# zigbee-plant-sensor-v1_1.net
KiCad netlist of a schematic drawn in EasyEDA Pro
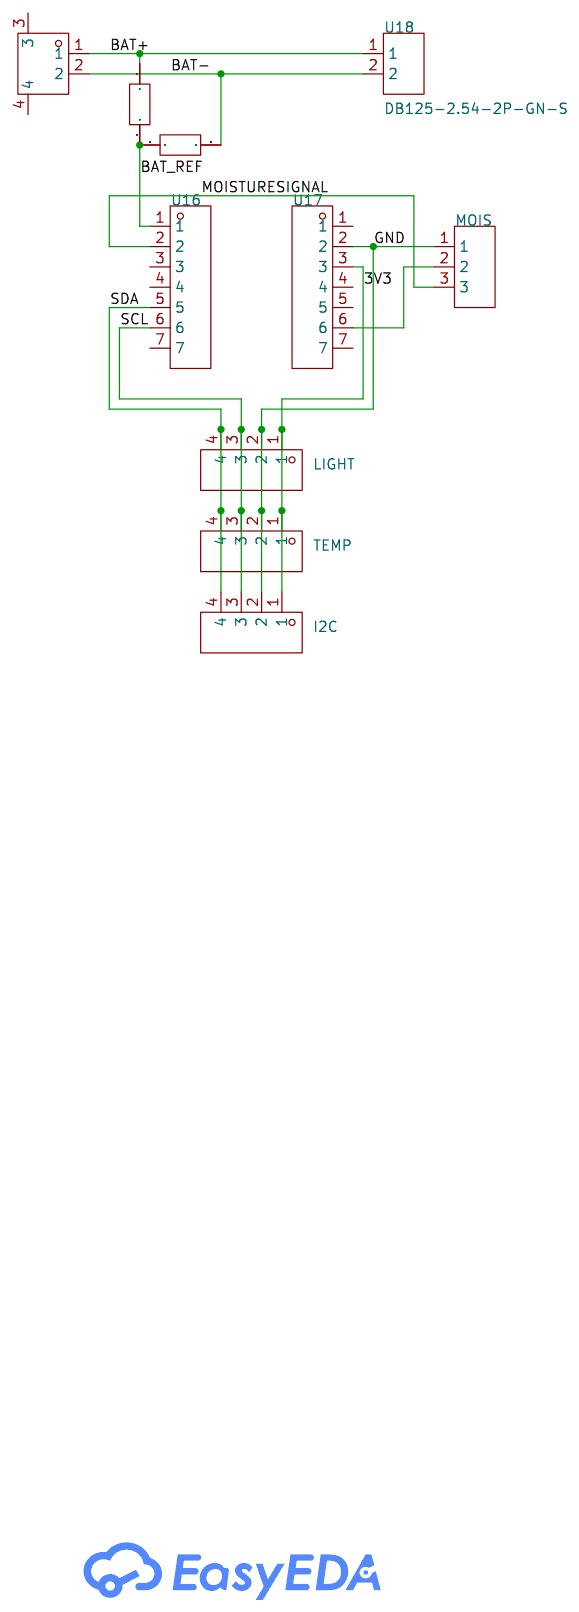
[diagram p0: schematic sheet]

(export (version "E")
  (design (tool "Eeschema 10.0.6"))
  (components
    (comp (ref "CN1")
      (value "JST-PH-2-SMT-RA")
      (footprint "easyedapro:CONN-SMD_JST-PH-2-SMT-RA")
      (libsource (lib "easyedapro") (part "JST-PH-2-SMT-RA"))
    )
    (comp (ref "I2C")
      (value "5BML8-11732-104-W0")
      (footprint "easyedapro:CONN-TH_5BML8-11732-104-W0")
      (fields (field (name "Manufacturer") "SAMZO(三佐)"))
      (libsource (lib "easyedapro") (part "5BML8-11732-104-W0"))
    )
    (comp (ref "LIGHT")
      (value "5BML8-11732-104-W0")
      (footprint "easyedapro:CONN-TH_5BML8-11732-104-W0")
      (fields (field (name "Manufacturer") "SAMZO(三佐)"))
      (libsource (lib "easyedapro") (part "5BML8-11732-104-W0"))
    )
    (comp (ref "MOIS")
      (value "HTSW-103-07-S-S")
      (footprint "easyedapro:HDR-TH_3P-P2.54-V-M-1")
      (fields (field (name "Manufacturer") "SAMTEC"))
      (libsource (lib "easyedapro") (part "HTSW-103-07-S-S"))
    )
    (comp (ref "R1")
      (value "200kΩ")
      (footprint "easyedapro:RES-TH_BD2.5-L7.0-P11.00-D0.6")
      (description "Type:Carbon Composite Resistor Resistance:200kΩ Tolerance:±5% Tolerance:±5% Power(Watts):250mW")
      (fields (field (name "Manufacturer Part") "OD204J") (field (name "Manufacturer") "Ohmite"))
      (libsource (lib "easyedapro") (part "OD204J"))
    )
    (comp (ref "R2")
      (value "200kΩ")
      (footprint "easyedapro:RES-TH_BD2.5-L7.0-P11.00-D0.6")
      (description "Type:Carbon Composite Resistor Resistance:200kΩ Tolerance:±5% Tolerance:±5% Power(Watts):250mW")
      (fields (field (name "Manufacturer Part") "OD204J") (field (name "Manufacturer") "Ohmite"))
      (libsource (lib "easyedapro") (part "OD204J"))
    )
    (comp (ref "TEMP")
      (value "5BML8-11732-104-W0")
      (footprint "easyedapro:CONN-TH_5BML8-11732-104-W0")
      (fields (field (name "Manufacturer") "SAMZO(三佐)"))
      (libsource (lib "easyedapro") (part "5BML8-11732-104-W0"))
    )
    (comp (ref "U16")
      (value "IPCP254F07PB08V")
      (footprint "easyedapro:HDR-TH_7P-P2.54-V-F")
      (fields (field (name "Manufacturer") "INCP"))
      (libsource (lib "easyedapro") (part "IPCP254F07PB08V"))
    )
    (comp (ref "U17")
      (value "IPCP254F07PB08V")
      (footprint "easyedapro:HDR-TH_7P-P2.54-V-F")
      (fields (field (name "Manufacturer") "INCP"))
      (libsource (lib "easyedapro") (part "IPCP254F07PB08V"))
    )
    (comp (ref "U18")
      (value "DB125-2.54-2P-GN-S")
      (footprint "easyedapro:CONN-TH_DB125-2.54-2P-GN")
      (fields (field (name "Manufacturer") "DORABO(地博电气)"))
      (libsource (lib "easyedapro") (part "DB125-2.54-2P-GN"))
    )
  )
  (nets
    (net (code "1") (name "/3V3") (class "Default")
      (node (ref "I2C") (pin "1") (pinfunction "1_1") (pintype "unspecified"))
      (node (ref "LIGHT") (pin "1") (pinfunction "1_1") (pintype "unspecified"))
      (node (ref "TEMP") (pin "1") (pinfunction "1_1") (pintype "unspecified"))
      (node (ref "U17") (pin "3") (pinfunction "3_3") (pintype "unspecified"))
    )
    (net (code "2") (name "/BAT+") (class "Default")
      (node (ref "CN1") (pin "1") (pinfunction "1_1") (pintype "unspecified"))
      (node (ref "R1") (pin "1") (pinfunction "1_1") (pintype "unspecified"))
      (node (ref "U18") (pin "1") (pinfunction "1_1") (pintype "unspecified"))
    )
    (net (code "3") (name "/BAT-") (class "Default")
      (node (ref "CN1") (pin "2") (pinfunction "2_2") (pintype "unspecified"))
      (node (ref "R2") (pin "2") (pinfunction "2_2") (pintype "unspecified"))
      (node (ref "U18") (pin "2") (pinfunction "2_2") (pintype "unspecified"))
    )
    (net (code "4") (name "/BAT_REF") (class "Default")
      (node (ref "R1") (pin "2") (pinfunction "2_2") (pintype "unspecified"))
      (node (ref "R2") (pin "1") (pinfunction "1_1") (pintype "unspecified"))
      (node (ref "U16") (pin "1") (pinfunction "1_1") (pintype "unspecified"))
    )
    (net (code "5") (name "/GND") (class "Default")
      (node (ref "I2C") (pin "2") (pinfunction "2_2") (pintype "unspecified"))
      (node (ref "LIGHT") (pin "2") (pinfunction "2_2") (pintype "unspecified"))
      (node (ref "MOIS") (pin "1") (pinfunction "1_1") (pintype "unspecified"))
      (node (ref "TEMP") (pin "2") (pinfunction "2_2") (pintype "unspecified"))
      (node (ref "U17") (pin "2") (pinfunction "2_2") (pintype "unspecified"))
    )
    (net (code "6") (name "/MOISTURESIGNAL") (class "Default")
      (node (ref "MOIS") (pin "3") (pinfunction "3_3") (pintype "unspecified"))
      (node (ref "U16") (pin "2") (pinfunction "2_2") (pintype "unspecified"))
    )
    (net (code "7") (name "/SCL") (class "Default")
      (node (ref "I2C") (pin "3") (pinfunction "3_3") (pintype "unspecified"))
      (node (ref "LIGHT") (pin "3") (pinfunction "3_3") (pintype "unspecified"))
      (node (ref "TEMP") (pin "3") (pinfunction "3_3") (pintype "unspecified"))
      (node (ref "U16") (pin "6") (pinfunction "6_6") (pintype "unspecified"))
    )
    (net (code "8") (name "/SDA") (class "Default")
      (node (ref "I2C") (pin "4") (pinfunction "4_4") (pintype "unspecified"))
      (node (ref "LIGHT") (pin "4") (pinfunction "4_4") (pintype "unspecified"))
      (node (ref "TEMP") (pin "4") (pinfunction "4_4") (pintype "unspecified"))
      (node (ref "U16") (pin "5") (pinfunction "5_5") (pintype "unspecified"))
    )
    (net (code "9") (name "Net-(MOIS-Pad2)") (class "Default")
      (node (ref "MOIS") (pin "2") (pinfunction "2_2") (pintype "unspecified"))
      (node (ref "U17") (pin "6") (pinfunction "6_6") (pintype "unspecified"))
    )
    (net (code "10") (name "unconnected-(CN1-Pad3)") (class "Default")
      (node (ref "CN1") (pin "3") (pinfunction "3_3") (pintype "unspecified"))
    )
    (net (code "11") (name "unconnected-(CN1-Pad4)") (class "Default")
      (node (ref "CN1") (pin "4") (pinfunction "4_4") (pintype "unspecified"))
    )
    (net (code "12") (name "unconnected-(U16-Pad3)") (class "Default")
      (node (ref "U16") (pin "3") (pinfunction "3_3") (pintype "unspecified"))
    )
    (net (code "13") (name "unconnected-(U16-Pad4)") (class "Default")
      (node (ref "U16") (pin "4") (pinfunction "4_4") (pintype "unspecified"))
    )
    (net (code "14") (name "unconnected-(U16-Pad7)") (class "Default")
      (node (ref "U16") (pin "7") (pinfunction "7_7") (pintype "unspecified"))
    )
    (net (code "15") (name "unconnected-(U17-Pad1)") (class "Default")
      (node (ref "U17") (pin "1") (pinfunction "1_1") (pintype "unspecified"))
    )
    (net (code "16") (name "unconnected-(U17-Pad4)") (class "Default")
      (node (ref "U17") (pin "4") (pinfunction "4_4") (pintype "unspecified"))
    )
    (net (code "17") (name "unconnected-(U17-Pad5)") (class "Default")
      (node (ref "U17") (pin "5") (pinfunction "5_5") (pintype "unspecified"))
    )
    (net (code "18") (name "unconnected-(U17-Pad7)") (class "Default")
      (node (ref "U17") (pin "7") (pinfunction "7_7") (pintype "unspecified"))
    )
  )
)
